# Sheet1.net
KiCad netlist of a schematic drawn in Altium Designer
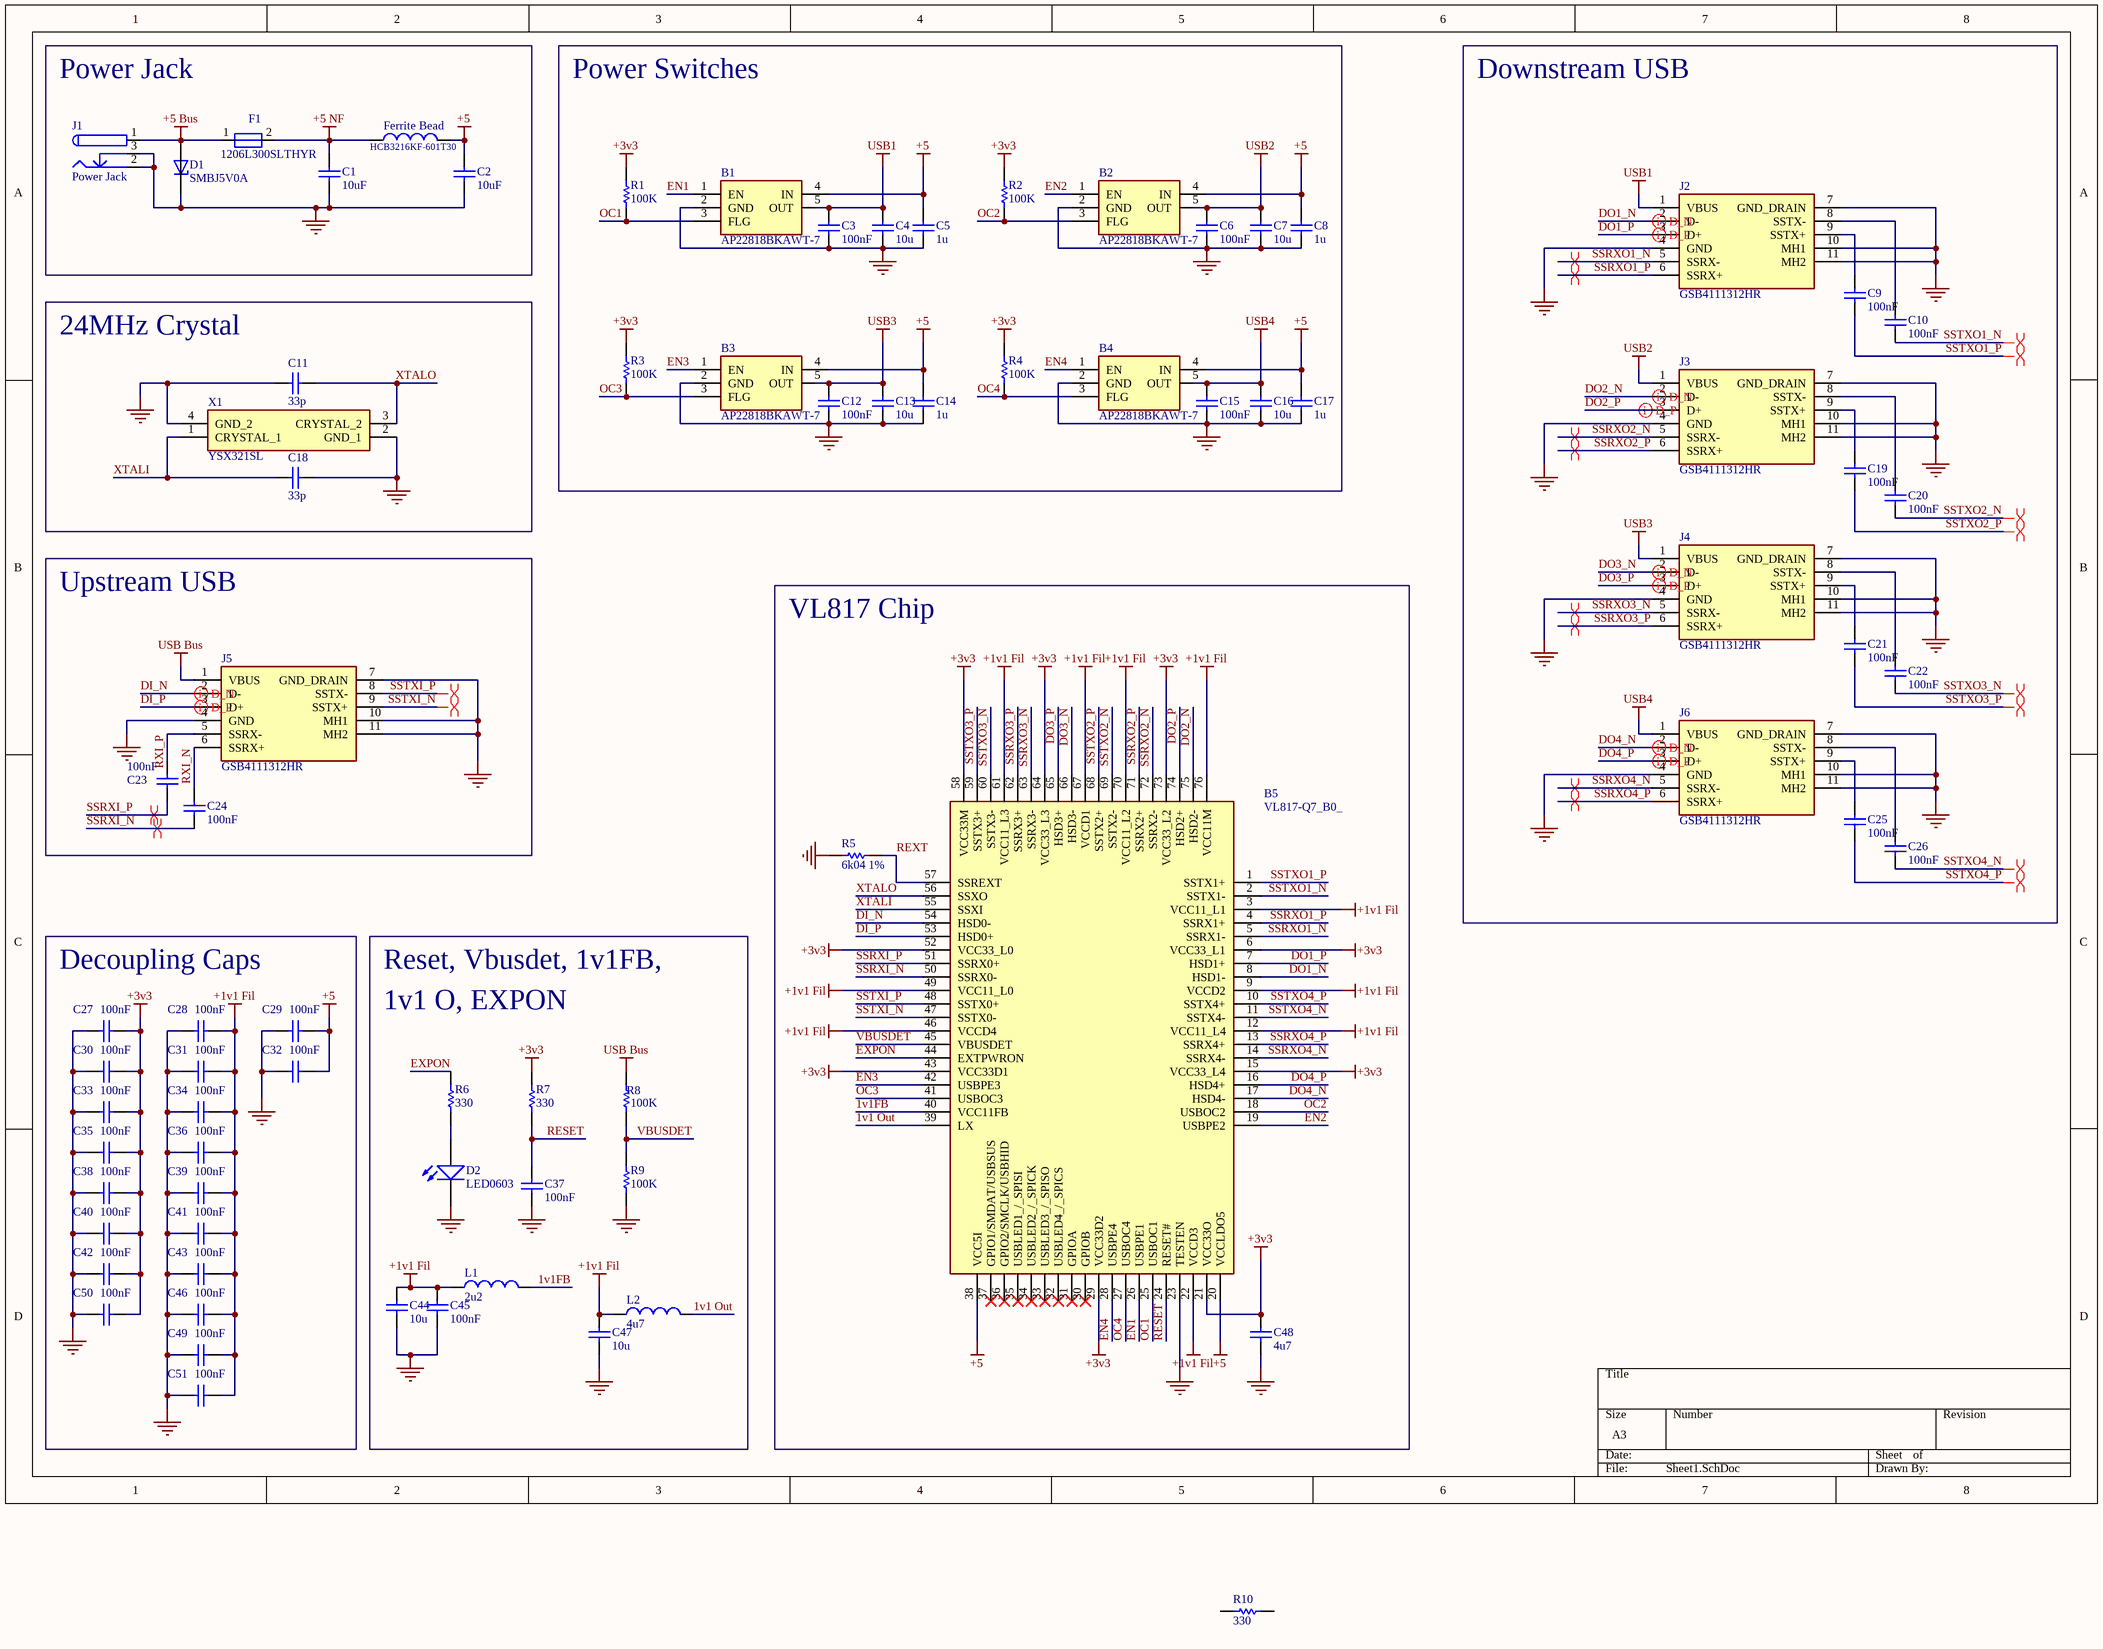
[diagram p0: Sheet1.SchDoc]

(export (version "E")
  (design (tool "Eeschema 10.0.6"))
  (components
    (comp (ref "B1")
      (value "AP22818BKAWT-7")
      (footprint "SOT95P280X100-5N")
      (description "USB Switch ICs USB Power Switch TSOT25 T&R 3K")
      (fields (field (name "MOUSER PART NUMBER") "621-AP22818BKAWT-7"))
      (libsource (lib "AP22818BKAWT-7") (part "AP22818BKAWT-7"))
    )
    (comp (ref "B2")
      (value "AP22818BKAWT-7")
      (footprint "SOT95P280X100-5N")
      (description "USB Switch ICs USB Power Switch TSOT25 T&R 3K")
      (fields (field (name "MOUSER PART NUMBER") "621-AP22818BKAWT-7"))
      (libsource (lib "AP22818BKAWT-7") (part "AP22818BKAWT-7"))
    )
    (comp (ref "B3")
      (value "AP22818BKAWT-7")
      (footprint "SOT95P280X100-5N")
      (description "USB Switch ICs USB Power Switch TSOT25 T&R 3K")
      (fields (field (name "MOUSER PART NUMBER") "621-AP22818BKAWT-7"))
      (libsource (lib "AP22818BKAWT-7") (part "AP22818BKAWT-7"))
    )
    (comp (ref "B4")
      (value "AP22818BKAWT-7")
      (footprint "SOT95P280X100-5N")
      (description "USB Switch ICs USB Power Switch TSOT25 T&R 3K")
      (fields (field (name "MOUSER PART NUMBER") "621-AP22818BKAWT-7"))
      (libsource (lib "AP22818BKAWT-7") (part "AP22818BKAWT-7"))
    )
    (comp (ref "B5")
      (value "VL817-Q7_B0_")
      (footprint "QFN40P900X900X90-77N-D")
      (description "QFN-76_9x9x04P USB ICs RoHS")
      (fields (field (name "MANUFACTURER_PART_NUMBER") "VL817-Q7(B0)"))
      (libsource (lib "VL817-Q7_B0_") (part "VL817-Q7_B0_"))
    )
    (comp (ref "C1")
      (value "10uF")
      (footprint "CAP1206")
      (description "CAP1206")
      (libsource (lib "CAP1206") (part "CAP1206"))
    )
    (comp (ref "C2")
      (value "10uF")
      (footprint "CAP1206")
      (description "CAP1206")
      (libsource (lib "CAP1206") (part "CAP1206"))
    )
    (comp (ref "C3")
      (value "100nF")
      (footprint "CAP0402")
      (description "CAP0402")
      (libsource (lib "CAP0402") (part "CAP0402"))
    )
    (comp (ref "C4")
      (value "10u")
      (footprint "CAP0603")
      (description "CAP0603")
      (libsource (lib "CAP0603") (part "CAP0603"))
    )
    (comp (ref "C5")
      (value "1u")
      (footprint "CAP0603")
      (description "CAP0603")
      (libsource (lib "CAP0603") (part "CAP0603"))
    )
    (comp (ref "C6")
      (value "100nF")
      (footprint "CAP0402")
      (description "CAP0402")
      (libsource (lib "CAP0402") (part "CAP0402"))
    )
    (comp (ref "C7")
      (value "10u")
      (footprint "CAP0603")
      (description "CAP0603")
      (libsource (lib "CAP0603") (part "CAP0603"))
    )
    (comp (ref "C8")
      (value "1u")
      (footprint "CAP0603")
      (description "CAP0603")
      (libsource (lib "CAP0603") (part "CAP0603"))
    )
    (comp (ref "C9")
      (value "100nF")
      (footprint "CAP0402")
      (description "CAP0402")
      (libsource (lib "CAP0402") (part "CAP0402"))
    )
    (comp (ref "C10")
      (value "100nF")
      (footprint "CAP0402")
      (description "CAP0402")
      (libsource (lib "CAP0402") (part "CAP0402"))
    )
    (comp (ref "C11")
      (value "33p")
      (footprint "CAP0402")
      (description "CAP0402")
      (libsource (lib "CAP0402") (part "CAP0402"))
    )
    (comp (ref "C12")
      (value "100nF")
      (footprint "CAP0402")
      (description "CAP0402")
      (libsource (lib "CAP0402") (part "CAP0402"))
    )
    (comp (ref "C13")
      (value "10u")
      (footprint "CAP0603")
      (description "CAP0603")
      (libsource (lib "CAP0603") (part "CAP0603"))
    )
    (comp (ref "C14")
      (value "1u")
      (footprint "CAP0603")
      (description "CAP0603")
      (libsource (lib "CAP0603") (part "CAP0603"))
    )
    (comp (ref "C15")
      (value "100nF")
      (footprint "CAP0402")
      (description "CAP0402")
      (libsource (lib "CAP0402") (part "CAP0402"))
    )
    (comp (ref "C16")
      (value "10u")
      (footprint "CAP0603")
      (description "CAP0603")
      (libsource (lib "CAP0603") (part "CAP0603"))
    )
    (comp (ref "C17")
      (value "1u")
      (footprint "CAP0603")
      (description "CAP0603")
      (libsource (lib "CAP0603") (part "CAP0603"))
    )
    (comp (ref "C18")
      (value "33p")
      (footprint "CAP0402")
      (description "CAP0402")
      (libsource (lib "CAP0402") (part "CAP0402"))
    )
    (comp (ref "C19")
      (value "100nF")
      (footprint "CAP0402")
      (description "CAP0402")
      (libsource (lib "CAP0402") (part "CAP0402"))
    )
    (comp (ref "C20")
      (value "100nF")
      (footprint "CAP0402")
      (description "CAP0402")
      (libsource (lib "CAP0402") (part "CAP0402"))
    )
    (comp (ref "C21")
      (value "100nF")
      (footprint "CAP0402")
      (description "CAP0402")
      (libsource (lib "CAP0402") (part "CAP0402"))
    )
    (comp (ref "C22")
      (value "100nF")
      (footprint "CAP0402")
      (description "CAP0402")
      (libsource (lib "CAP0402") (part "CAP0402"))
    )
    (comp (ref "C23")
      (value "100nF")
      (footprint "CAP0402")
      (description "CAP0402")
      (libsource (lib "CAP0402") (part "CAP0402"))
    )
    (comp (ref "C24")
      (value "100nF")
      (footprint "CAP0402")
      (description "CAP0402")
      (libsource (lib "CAP0402") (part "CAP0402"))
    )
    (comp (ref "C25")
      (value "100nF")
      (footprint "CAP0402")
      (description "CAP0402")
      (libsource (lib "CAP0402") (part "CAP0402"))
    )
    (comp (ref "C26")
      (value "100nF")
      (footprint "CAP0402")
      (description "CAP0402")
      (libsource (lib "CAP0402") (part "CAP0402"))
    )
    (comp (ref "C27")
      (value "100nF")
      (footprint "CAP0402")
      (description "CAP0402")
      (libsource (lib "CAP0402") (part "CAP0402"))
    )
    (comp (ref "C28")
      (value "100nF")
      (footprint "CAP0402")
      (description "CAP0402")
      (libsource (lib "CAP0402") (part "CAP0402"))
    )
    (comp (ref "C29")
      (value "100nF")
      (footprint "CAP0402")
      (description "CAP0402")
      (libsource (lib "CAP0402") (part "CAP0402"))
    )
    (comp (ref "C30")
      (value "100nF")
      (footprint "CAP0402")
      (description "CAP0402")
      (libsource (lib "CAP0402") (part "CAP0402"))
    )
    (comp (ref "C31")
      (value "100nF")
      (footprint "CAP0402")
      (description "CAP0402")
      (libsource (lib "CAP0402") (part "CAP0402"))
    )
    (comp (ref "C32")
      (value "100nF")
      (footprint "CAP0402")
      (description "CAP0402")
      (libsource (lib "CAP0402") (part "CAP0402"))
    )
    (comp (ref "C33")
      (value "100nF")
      (footprint "CAP0402")
      (description "CAP0402")
      (libsource (lib "CAP0402") (part "CAP0402"))
    )
    (comp (ref "C34")
      (value "100nF")
      (footprint "CAP0402")
      (description "CAP0402")
      (libsource (lib "CAP0402") (part "CAP0402"))
    )
    (comp (ref "C35")
      (value "100nF")
      (footprint "CAP0402")
      (description "CAP0402")
      (libsource (lib "CAP0402") (part "CAP0402"))
    )
    (comp (ref "C36")
      (value "100nF")
      (footprint "CAP0402")
      (description "CAP0402")
      (libsource (lib "CAP0402") (part "CAP0402"))
    )
    (comp (ref "C37")
      (value "100nF")
      (footprint "CAP0402")
      (description "CAP0402")
      (libsource (lib "CAP0402") (part "CAP0402"))
    )
    (comp (ref "C38")
      (value "100nF")
      (footprint "CAP0402")
      (description "CAP0402")
      (libsource (lib "CAP0402") (part "CAP0402"))
    )
    (comp (ref "C39")
      (value "100nF")
      (footprint "CAP0402")
      (description "CAP0402")
      (libsource (lib "CAP0402") (part "CAP0402"))
    )
    (comp (ref "C40")
      (value "100nF")
      (footprint "CAP0402")
      (description "CAP0402")
      (libsource (lib "CAP0402") (part "CAP0402"))
    )
    (comp (ref "C41")
      (value "100nF")
      (footprint "CAP0402")
      (description "CAP0402")
      (libsource (lib "CAP0402") (part "CAP0402"))
    )
    (comp (ref "C42")
      (value "100nF")
      (footprint "CAP0402")
      (description "CAP0402")
      (libsource (lib "CAP0402") (part "CAP0402"))
    )
    (comp (ref "C43")
      (value "100nF")
      (footprint "CAP0402")
      (description "CAP0402")
      (libsource (lib "CAP0402") (part "CAP0402"))
    )
    (comp (ref "C44")
      (value "10u")
      (footprint "CAP0603")
      (description "CAP0603")
      (libsource (lib "CAP0603") (part "CAP0603"))
    )
    (comp (ref "C45")
      (value "100nF")
      (footprint "CAP0402")
      (description "CAP0402")
      (libsource (lib "CAP0402") (part "CAP0402"))
    )
    (comp (ref "C46")
      (value "100nF")
      (footprint "CAP0402")
      (description "CAP0402")
      (libsource (lib "CAP0402") (part "CAP0402"))
    )
    (comp (ref "C47")
      (value "10u")
      (footprint "CAP0603")
      (description "CAP0603")
      (libsource (lib "CAP0603") (part "CAP0603"))
    )
    (comp (ref "C48")
      (value "4u7")
      (footprint "CAP0603")
      (description "CAP0603")
      (libsource (lib "CAP0603") (part "CAP0603"))
    )
    (comp (ref "C49")
      (value "100nF")
      (footprint "CAP0402")
      (description "CAP0402")
      (libsource (lib "CAP0402") (part "CAP0402"))
    )
    (comp (ref "C50")
      (value "100nF")
      (footprint "CAP0402")
      (description "CAP0402")
      (libsource (lib "CAP0402") (part "CAP0402"))
    )
    (comp (ref "C51")
      (value "100nF")
      (footprint "CAP0402")
      (description "CAP0402")
      (libsource (lib "CAP0402") (part "CAP0402"))
    )
    (comp (ref "D1")
      (value "SMBJ5V0A")
      (footprint "DIOM4336X265N")
      (fields (field (name "MF") "Fairchild Semiconductor"))
      (libsource (lib "SMBJ5V0A") (part "SMBJ5V0A"))
    )
    (comp (ref "D2")
      (value "LED0603")
      (footprint "LED_SMD_0603")
      (libsource (lib "LED_SMD_0603") (part "LED_SMD_0603"))
    )
    (comp (ref "F1")
      (value "1206L300SLTHYR")
      (footprint "FUSC3115X66N")
      (description "475 Series 1206 Fast-Acting Fuse")
      (fields (field (name "MF") "Littelfuse") (field (name "MP") "046602.5NRHF"))
      (libsource (lib "046602.5NRHF") (part "046602.5NRHF"))
    )
    (comp (ref "Ferrite Bead")
      (value "HCB3216KF-601T30")
      (footprint "IND1206")
      (description "IND1206")
      (libsource (lib "IND1206") (part "IND1206"))
    )
    (comp (ref "J1")
      (value "Power Jack")
      (footprint "Power Jack")
      (fields (field (name "DESIGNER") "Saeid Jorablo"))
      (libsource (lib "Library 1") (part "Power Jack"))
    )
    (comp (ref "J2")
      (value "GSB4111312HR")
      (footprint "GSB4111312HR")
      (libsource (lib "GSB4111312HR") (part "GSB4111312HR"))
    )
    (comp (ref "J3")
      (value "GSB4111312HR")
      (footprint "GSB4111312HR")
      (libsource (lib "GSB4111312HR") (part "GSB4111312HR"))
    )
    (comp (ref "J4")
      (value "GSB4111312HR")
      (footprint "GSB4111312HR")
      (libsource (lib "GSB4111312HR") (part "GSB4111312HR"))
    )
    (comp (ref "J5")
      (value "GSB4111312HR")
      (footprint "GSB4111312HR")
      (libsource (lib "GSB4111312HR") (part "GSB4111312HR"))
    )
    (comp (ref "J6")
      (value "GSB4111312HR")
      (footprint "GSB4111312HR")
      (libsource (lib "GSB4111312HR") (part "GSB4111312HR"))
    )
    (comp (ref "L1")
      (value "2u2")
      (footprint "IND0603")
      (description "IND0603")
      (libsource (lib "IND0603") (part "IND0603"))
    )
    (comp (ref "L2")
      (value "4u7")
      (footprint "IND0603")
      (description "IND0603")
      (libsource (lib "IND0603") (part "IND0603"))
    )
    (comp (ref "R1")
      (value "100K")
      (footprint "RES0603")
      (description "RES0603")
      (libsource (lib "RES0603") (part "RES0603"))
    )
    (comp (ref "R2")
      (value "100K")
      (footprint "RES0603")
      (description "RES0603")
      (libsource (lib "RES0603") (part "RES0603"))
    )
    (comp (ref "R3")
      (value "100K")
      (footprint "RES0603")
      (description "RES0603")
      (libsource (lib "RES0603") (part "RES0603"))
    )
    (comp (ref "R4")
      (value "100K")
      (footprint "RES0603")
      (description "RES0603")
      (libsource (lib "RES0603") (part "RES0603"))
    )
    (comp (ref "R5")
      (value "6k04 1%")
      (footprint "RES0603")
      (description "RES0603")
      (libsource (lib "RES0603") (part "RES0603"))
    )
    (comp (ref "R6")
      (value "330")
      (footprint "RES0603")
      (description "RES0603")
      (libsource (lib "RES0603") (part "RES0603"))
    )
    (comp (ref "R7")
      (value "330")
      (footprint "RES0603")
      (description "RES0603")
      (libsource (lib "RES0603") (part "RES0603"))
    )
    (comp (ref "R8")
      (value "100K")
      (footprint "RES0603")
      (description "RES0603")
      (libsource (lib "RES0603") (part "RES0603"))
    )
    (comp (ref "R9")
      (value "100K")
      (footprint "RES0603")
      (description "RES0603")
      (libsource (lib "RES0603") (part "RES0603"))
    )
    (comp (ref "R10")
      (value "330")
      (footprint "Res50")
      (description "Resistor 0.5")
      (fields
        (field (name "Comment") "Resistor vertical")
        (field (name "PUBLISHER") "Seyed mohsen ghasemian")
      )
      (libsource (lib "usefully_Library") (part "Resistor vertical"))
    )
    (comp (ref "X1")
      (value "YSX321SL")
      (footprint "YSX321SL")
      (description "Crystal")
      (libsource (lib "YSX321SL") (part "YSX321SL"))
    )
  )
  (nets
    (net (code "1") (name "+1v1 Fil") (class "Default")
      (node (ref "B5") (pin "12") (pinfunction "VCC11_L4_12") (pintype "passive"))
      (node (ref "B5") (pin "22") (pinfunction "VCCD3_22") (pintype "passive"))
      (node (ref "B5") (pin "3") (pinfunction "VCC11_L1_3") (pintype "passive"))
      (node (ref "B5") (pin "46") (pinfunction "VCCD4_46") (pintype "passive"))
      (node (ref "B5") (pin "49") (pinfunction "VCC11_L0_49") (pintype "passive"))
      (node (ref "B5") (pin "61") (pinfunction "VCC11_L3_61") (pintype "passive"))
      (node (ref "B5") (pin "67") (pinfunction "VCCD1_67") (pintype "passive"))
      (node (ref "B5") (pin "70") (pinfunction "VCC11_L2_70") (pintype "passive"))
      (node (ref "B5") (pin "76") (pinfunction "VCC11M_76") (pintype "passive"))
      (node (ref "B5") (pin "9") (pinfunction "VCCD2_9") (pintype "passive"))
      (node (ref "C28") (pin "2") (pinfunction "2_2") (pintype "passive"))
      (node (ref "C31") (pin "2") (pinfunction "2_2") (pintype "passive"))
      (node (ref "C34") (pin "2") (pinfunction "2_2") (pintype "passive"))
      (node (ref "C36") (pin "2") (pinfunction "2_2") (pintype "passive"))
      (node (ref "C39") (pin "2") (pinfunction "2_2") (pintype "passive"))
      (node (ref "C41") (pin "2") (pinfunction "2_2") (pintype "passive"))
      (node (ref "C43") (pin "2") (pinfunction "2_2") (pintype "passive"))
      (node (ref "C44") (pin "2") (pinfunction "2_2") (pintype "passive"))
      (node (ref "C45") (pin "2") (pinfunction "2_2") (pintype "passive"))
      (node (ref "C46") (pin "2") (pinfunction "2_2") (pintype "passive"))
      (node (ref "C47") (pin "2") (pinfunction "2_2") (pintype "passive"))
      (node (ref "C49") (pin "2") (pinfunction "2_2") (pintype "passive"))
      (node (ref "C51") (pin "2") (pinfunction "2_2") (pintype "passive"))
      (node (ref "L1") (pin "1") (pinfunction "1_1") (pintype "passive"))
      (node (ref "L2") (pin "1") (pinfunction "1_1") (pintype "passive"))
    )
    (net (code "2") (name "+3v3") (class "Default")
      (node (ref "B5") (pin "15") (pinfunction "VCC33_L4_15") (pintype "passive"))
      (node (ref "B5") (pin "21") (pinfunction "VCC33O_21") (pintype "passive"))
      (node (ref "B5") (pin "29") (pinfunction "VCC33D2_29") (pintype "passive"))
      (node (ref "B5") (pin "43") (pinfunction "VCC33D1_43") (pintype "passive"))
      (node (ref "B5") (pin "52") (pinfunction "VCC33_L0_52") (pintype "passive"))
      (node (ref "B5") (pin "58") (pinfunction "VCC33M_58") (pintype "passive"))
      (node (ref "B5") (pin "6") (pinfunction "VCC33_L1_6") (pintype "passive"))
      (node (ref "B5") (pin "64") (pinfunction "VCC33_L3_64") (pintype "passive"))
      (node (ref "B5") (pin "73") (pinfunction "VCC33_L2_73") (pintype "passive"))
      (node (ref "C27") (pin "2") (pinfunction "2_2") (pintype "passive"))
      (node (ref "C30") (pin "2") (pinfunction "2_2") (pintype "passive"))
      (node (ref "C33") (pin "2") (pinfunction "2_2") (pintype "passive"))
      (node (ref "C35") (pin "2") (pinfunction "2_2") (pintype "passive"))
      (node (ref "C38") (pin "2") (pinfunction "2_2") (pintype "passive"))
      (node (ref "C40") (pin "2") (pinfunction "2_2") (pintype "passive"))
      (node (ref "C42") (pin "2") (pinfunction "2_2") (pintype "passive"))
      (node (ref "C48") (pin "2") (pinfunction "2_2") (pintype "passive"))
      (node (ref "C50") (pin "2") (pinfunction "2_2") (pintype "passive"))
      (node (ref "R1") (pin "2") (pinfunction "2_2") (pintype "passive"))
      (node (ref "R2") (pin "2") (pinfunction "2_2") (pintype "passive"))
      (node (ref "R3") (pin "2") (pinfunction "2_2") (pintype "passive"))
      (node (ref "R4") (pin "2") (pinfunction "2_2") (pintype "passive"))
      (node (ref "R7") (pin "2") (pinfunction "2_2") (pintype "passive"))
    )
    (net (code "3") (name "+5") (class "Default")
      (node (ref "B1") (pin "4") (pinfunction "IN_4") (pintype "passive"))
      (node (ref "B2") (pin "4") (pinfunction "IN_4") (pintype "passive"))
      (node (ref "B3") (pin "4") (pinfunction "IN_4") (pintype "passive"))
      (node (ref "B4") (pin "4") (pinfunction "IN_4") (pintype "passive"))
      (node (ref "B5") (pin "20") (pinfunction "VCCLDO5_20") (pintype "passive"))
      (node (ref "B5") (pin "38") (pinfunction "VCC5I_38") (pintype "passive"))
      (node (ref "C14") (pin "2") (pinfunction "2_2") (pintype "passive"))
      (node (ref "C17") (pin "2") (pinfunction "2_2") (pintype "passive"))
      (node (ref "C2") (pin "2") (pinfunction "2_2") (pintype "passive"))
      (node (ref "C29") (pin "2") (pinfunction "2_2") (pintype "passive"))
      (node (ref "C32") (pin "2") (pinfunction "2_2") (pintype "passive"))
      (node (ref "C5") (pin "2") (pinfunction "2_2") (pintype "passive"))
      (node (ref "C8") (pin "2") (pinfunction "2_2") (pintype "passive"))
      (node (ref "Ferrite Bead") (pin "2") (pinfunction "2_2") (pintype "passive"))
    )
    (net (code "4") (name "+5 Bus") (class "Default")
      (node (ref "D1") (pin "A") (pinfunction "A_A") (pintype "passive"))
      (node (ref "F1") (pin "1") (pinfunction "1_1") (pintype "passive"))
      (node (ref "J1") (pin "1") (pinfunction "1_1") (pintype "power_in"))
    )
    (net (code "5") (name "+5 NF") (class "Default")
      (node (ref "C1") (pin "2") (pinfunction "2_2") (pintype "passive"))
      (node (ref "F1") (pin "2") (pinfunction "2_2") (pintype "passive"))
      (node (ref "Ferrite Bead") (pin "1") (pinfunction "1_1") (pintype "passive"))
    )
    (net (code "6") (name "/1v1 Out") (class "Default")
      (node (ref "B5") (pin "39") (pinfunction "LX_39") (pintype "passive"))
      (node (ref "L2") (pin "2") (pinfunction "2_2") (pintype "passive"))
    )
    (net (code "7") (name "/1v1FB") (class "Default")
      (node (ref "B5") (pin "40") (pinfunction "VCC11FB_40") (pintype "passive"))
      (node (ref "L1") (pin "2") (pinfunction "2_2") (pintype "passive"))
    )
    (net (code "8") (name "/DI_N") (class "Default")
      (node (ref "B5") (pin "54") (pinfunction "HSD0-_54") (pintype "passive"))
      (node (ref "J5") (pin "2") (pinfunction "D-_2") (pintype "passive"))
    )
    (net (code "9") (name "/DI_P") (class "Default")
      (node (ref "B5") (pin "53") (pinfunction "HSD0+_53") (pintype "passive"))
      (node (ref "J5") (pin "3") (pinfunction "D+_3") (pintype "passive"))
    )
    (net (code "10") (name "/DO1_N") (class "Default")
      (node (ref "B5") (pin "8") (pinfunction "HSD1-_8") (pintype "passive"))
      (node (ref "J2") (pin "2") (pinfunction "D-_2") (pintype "passive"))
    )
    (net (code "11") (name "/DO1_P") (class "Default")
      (node (ref "B5") (pin "7") (pinfunction "HSD1+_7") (pintype "passive"))
      (node (ref "J2") (pin "3") (pinfunction "D+_3") (pintype "passive"))
    )
    (net (code "12") (name "/DO2_N") (class "Default")
      (node (ref "B5") (pin "75") (pinfunction "HSD2-_75") (pintype "passive"))
      (node (ref "J3") (pin "2") (pinfunction "D-_2") (pintype "passive"))
    )
    (net (code "13") (name "/DO2_P") (class "Default")
      (node (ref "B5") (pin "74") (pinfunction "HSD2+_74") (pintype "passive"))
      (node (ref "J3") (pin "3") (pinfunction "D+_3") (pintype "passive"))
    )
    (net (code "14") (name "/DO3_N") (class "Default")
      (node (ref "B5") (pin "66") (pinfunction "HSD3-_66") (pintype "passive"))
      (node (ref "J4") (pin "2") (pinfunction "D-_2") (pintype "passive"))
    )
    (net (code "15") (name "/DO3_P") (class "Default")
      (node (ref "B5") (pin "65") (pinfunction "HSD3+_65") (pintype "passive"))
      (node (ref "J4") (pin "3") (pinfunction "D+_3") (pintype "passive"))
    )
    (net (code "16") (name "/DO4_N") (class "Default")
      (node (ref "B5") (pin "17") (pinfunction "HSD4-_17") (pintype "passive"))
      (node (ref "J6") (pin "2") (pinfunction "D-_2") (pintype "passive"))
    )
    (net (code "17") (name "/DO4_P") (class "Default")
      (node (ref "B5") (pin "16") (pinfunction "HSD4+_16") (pintype "passive"))
      (node (ref "J6") (pin "3") (pinfunction "D+_3") (pintype "passive"))
    )
    (net (code "18") (name "/EN1") (class "Default")
      (node (ref "B1") (pin "1") (pinfunction "EN_1") (pintype "passive"))
      (node (ref "B5") (pin "26") (pinfunction "USBPE1_26") (pintype "passive"))
    )
    (net (code "19") (name "/EN2") (class "Default")
      (node (ref "B2") (pin "1") (pinfunction "EN_1") (pintype "passive"))
      (node (ref "B5") (pin "19") (pinfunction "USBPE2_19") (pintype "passive"))
    )
    (net (code "20") (name "/EN3") (class "Default")
      (node (ref "B3") (pin "1") (pinfunction "EN_1") (pintype "passive"))
      (node (ref "B5") (pin "42") (pinfunction "USBPE3_42") (pintype "passive"))
    )
    (net (code "21") (name "/EN4") (class "Default")
      (node (ref "B4") (pin "1") (pinfunction "EN_1") (pintype "passive"))
      (node (ref "B5") (pin "28") (pinfunction "USBPE4_28") (pintype "passive"))
    )
    (net (code "22") (name "/EXPON") (class "Default")
      (node (ref "B5") (pin "44") (pinfunction "EXTPWRON_44") (pintype "passive"))
      (node (ref "R6") (pin "2") (pinfunction "2_2") (pintype "passive"))
    )
    (net (code "23") (name "/OC1") (class "Default")
      (node (ref "B1") (pin "3") (pinfunction "FLG_3") (pintype "passive"))
      (node (ref "B5") (pin "25") (pinfunction "USBOC1_25") (pintype "passive"))
      (node (ref "R1") (pin "1") (pinfunction "1_1") (pintype "passive"))
    )
    (net (code "24") (name "/OC2") (class "Default")
      (node (ref "B2") (pin "3") (pinfunction "FLG_3") (pintype "passive"))
      (node (ref "B5") (pin "18") (pinfunction "USBOC2_18") (pintype "passive"))
      (node (ref "R2") (pin "1") (pinfunction "1_1") (pintype "passive"))
    )
    (net (code "25") (name "/OC3") (class "Default")
      (node (ref "B3") (pin "3") (pinfunction "FLG_3") (pintype "passive"))
      (node (ref "B5") (pin "41") (pinfunction "USBOC3_41") (pintype "passive"))
      (node (ref "R3") (pin "1") (pinfunction "1_1") (pintype "passive"))
    )
    (net (code "26") (name "/OC4") (class "Default")
      (node (ref "B4") (pin "3") (pinfunction "FLG_3") (pintype "passive"))
      (node (ref "B5") (pin "27") (pinfunction "USBOC4_27") (pintype "passive"))
      (node (ref "R4") (pin "1") (pinfunction "1_1") (pintype "passive"))
    )
    (net (code "27") (name "/RESET") (class "Default")
      (node (ref "B5") (pin "24") (pinfunction "RESET#_24") (pintype "passive"))
      (node (ref "C37") (pin "2") (pinfunction "2_2") (pintype "passive"))
      (node (ref "R7") (pin "1") (pinfunction "1_1") (pintype "passive"))
    )
    (net (code "28") (name "/REXT") (class "Default")
      (node (ref "B5") (pin "57") (pinfunction "SSREXT_57") (pintype "passive"))
      (node (ref "R5") (pin "1") (pinfunction "1_1") (pintype "passive"))
    )
    (net (code "29") (name "/RXI_N") (class "Default")
      (node (ref "C24") (pin "2") (pinfunction "2_2") (pintype "passive"))
      (node (ref "J5") (pin "6") (pinfunction "SSRX+_6") (pintype "passive"))
    )
    (net (code "30") (name "/RXI_P") (class "Default")
      (node (ref "C23") (pin "2") (pinfunction "2_2") (pintype "passive"))
      (node (ref "J5") (pin "5") (pinfunction "SSRX-_5") (pintype "passive"))
    )
    (net (code "31") (name "/SSRXI_N") (class "Default")
      (node (ref "B5") (pin "50") (pinfunction "SSRX0-_50") (pintype "passive"))
      (node (ref "C24") (pin "1") (pinfunction "1_1") (pintype "passive"))
    )
    (net (code "32") (name "/SSRXI_P") (class "Default")
      (node (ref "B5") (pin "51") (pinfunction "SSRX0+_51") (pintype "passive"))
      (node (ref "C23") (pin "1") (pinfunction "1_1") (pintype "passive"))
    )
    (net (code "33") (name "/SSRXO1_N") (class "Default")
      (node (ref "B5") (pin "5") (pinfunction "SSRX1-_5") (pintype "passive"))
      (node (ref "J2") (pin "5") (pinfunction "SSRX-_5") (pintype "passive"))
    )
    (net (code "34") (name "/SSRXO1_P") (class "Default")
      (node (ref "B5") (pin "4") (pinfunction "SSRX1+_4") (pintype "passive"))
      (node (ref "J2") (pin "6") (pinfunction "SSRX+_6") (pintype "passive"))
    )
    (net (code "35") (name "/SSRXO2_N") (class "Default")
      (node (ref "B5") (pin "72") (pinfunction "SSRX2-_72") (pintype "passive"))
      (node (ref "J3") (pin "5") (pinfunction "SSRX-_5") (pintype "passive"))
    )
    (net (code "36") (name "/SSRXO2_P") (class "Default")
      (node (ref "B5") (pin "71") (pinfunction "SSRX2+_71") (pintype "passive"))
      (node (ref "J3") (pin "6") (pinfunction "SSRX+_6") (pintype "passive"))
    )
    (net (code "37") (name "/SSRXO3_N") (class "Default")
      (node (ref "B5") (pin "63") (pinfunction "SSRX3-_63") (pintype "passive"))
      (node (ref "J4") (pin "5") (pinfunction "SSRX-_5") (pintype "passive"))
    )
    (net (code "38") (name "/SSRXO3_P") (class "Default")
      (node (ref "B5") (pin "62") (pinfunction "SSRX3+_62") (pintype "passive"))
      (node (ref "J4") (pin "6") (pinfunction "SSRX+_6") (pintype "passive"))
    )
    (net (code "39") (name "/SSRXO4_N") (class "Default")
      (node (ref "B5") (pin "14") (pinfunction "SSRX4-_14") (pintype "passive"))
      (node (ref "J6") (pin "5") (pinfunction "SSRX-_5") (pintype "passive"))
    )
    (net (code "40") (name "/SSRXO4_P") (class "Default")
      (node (ref "B5") (pin "13") (pinfunction "SSRX4+_13") (pintype "passive"))
      (node (ref "J6") (pin "6") (pinfunction "SSRX+_6") (pintype "passive"))
    )
    (net (code "41") (name "/SSTXI_N") (class "Default")
      (node (ref "B5") (pin "47") (pinfunction "SSTX0-_47") (pintype "passive"))
      (node (ref "J5") (pin "9") (pinfunction "SSTX+_9") (pintype "passive"))
    )
    (net (code "42") (name "/SSTXI_P") (class "Default")
      (node (ref "B5") (pin "48") (pinfunction "SSTX0+_48") (pintype "passive"))
      (node (ref "J5") (pin "8") (pinfunction "SSTX-_8") (pintype "passive"))
    )
    (net (code "43") (name "/SSTXO1_N") (class "Default")
      (node (ref "B5") (pin "2") (pinfunction "SSTX1-_2") (pintype "passive"))
      (node (ref "C10") (pin "1") (pinfunction "1_1") (pintype "passive"))
    )
    (net (code "44") (name "/SSTXO1_P") (class "Default")
      (node (ref "B5") (pin "1") (pinfunction "SSTX1+_1") (pintype "passive"))
      (node (ref "C9") (pin "1") (pinfunction "1_1") (pintype "passive"))
    )
    (net (code "45") (name "/SSTXO2_N") (class "Default")
      (node (ref "B5") (pin "69") (pinfunction "SSTX2-_69") (pintype "passive"))
      (node (ref "C20") (pin "1") (pinfunction "1_1") (pintype "passive"))
    )
    (net (code "46") (name "/SSTXO2_P") (class "Default")
      (node (ref "B5") (pin "68") (pinfunction "SSTX2+_68") (pintype "passive"))
      (node (ref "C19") (pin "1") (pinfunction "1_1") (pintype "passive"))
    )
    (net (code "47") (name "/SSTXO3_N") (class "Default")
      (node (ref "B5") (pin "60") (pinfunction "SSTX3-_60") (pintype "passive"))
      (node (ref "C22") (pin "1") (pinfunction "1_1") (pintype "passive"))
    )
    (net (code "48") (name "/SSTXO3_P") (class "Default")
      (node (ref "B5") (pin "59") (pinfunction "SSTX3+_59") (pintype "passive"))
      (node (ref "C21") (pin "1") (pinfunction "1_1") (pintype "passive"))
    )
    (net (code "49") (name "/SSTXO4_N") (class "Default")
      (node (ref "B5") (pin "11") (pinfunction "SSTX4-_11") (pintype "passive"))
      (node (ref "C26") (pin "1") (pinfunction "1_1") (pintype "passive"))
    )
    (net (code "50") (name "/SSTXO4_P") (class "Default")
      (node (ref "B5") (pin "10") (pinfunction "SSTX4+_10") (pintype "passive"))
      (node (ref "C25") (pin "1") (pinfunction "1_1") (pintype "passive"))
    )
    (net (code "51") (name "/VBUSDET") (class "Default")
      (node (ref "B5") (pin "45") (pinfunction "VBUSDET_45") (pintype "passive"))
      (node (ref "R8") (pin "1") (pinfunction "1_1") (pintype "passive"))
      (node (ref "R9") (pin "2") (pinfunction "2_2") (pintype "passive"))
    )
    (net (code "52") (name "/XTALI") (class "Default")
      (node (ref "B5") (pin "55") (pinfunction "SSXI_55") (pintype "passive"))
      (node (ref "C18") (pin "2") (pinfunction "2_2") (pintype "passive"))
      (node (ref "X1") (pin "1") (pinfunction "CRYSTAL_1_1") (pintype "passive"))
    )
    (net (code "53") (name "/XTALO") (class "Default")
      (node (ref "B5") (pin "56") (pinfunction "SSXO_56") (pintype "passive"))
      (node (ref "C11") (pin "1") (pinfunction "1_1") (pintype "passive"))
      (node (ref "X1") (pin "3") (pinfunction "CRYSTAL_2_3") (pintype "passive"))
    )
    (net (code "54") (name "GND") (class "Default")
      (node (ref "B1") (pin "2") (pinfunction "GND_2") (pintype "passive"))
      (node (ref "B2") (pin "2") (pinfunction "GND_2") (pintype "passive"))
      (node (ref "B3") (pin "2") (pinfunction "GND_2") (pintype "passive"))
      (node (ref "B4") (pin "2") (pinfunction "GND_2") (pintype "passive"))
      (node (ref "B5") (pin "23") (pinfunction "TESTEN_23") (pintype "passive"))
      (node (ref "C1") (pin "1") (pinfunction "1_1") (pintype "passive"))
      (node (ref "C11") (pin "2") (pinfunction "2_2") (pintype "passive"))
      (node (ref "C12") (pin "1") (pinfunction "1_1") (pintype "passive"))
      (node (ref "C13") (pin "1") (pinfunction "1_1") (pintype "passive"))
      (node (ref "C14") (pin "1") (pinfunction "1_1") (pintype "passive"))
      (node (ref "C15") (pin "1") (pinfunction "1_1") (pintype "passive"))
      (node (ref "C16") (pin "1") (pinfunction "1_1") (pintype "passive"))
      (node (ref "C17") (pin "1") (pinfunction "1_1") (pintype "passive"))
      (node (ref "C18") (pin "1") (pinfunction "1_1") (pintype "passive"))
      (node (ref "C2") (pin "1") (pinfunction "1_1") (pintype "passive"))
      (node (ref "C27") (pin "1") (pinfunction "1_1") (pintype "passive"))
      (node (ref "C28") (pin "1") (pinfunction "1_1") (pintype "passive"))
      (node (ref "C29") (pin "1") (pinfunction "1_1") (pintype "passive"))
      (node (ref "C3") (pin "1") (pinfunction "1_1") (pintype "passive"))
      (node (ref "C30") (pin "1") (pinfunction "1_1") (pintype "passive"))
      (node (ref "C31") (pin "1") (pinfunction "1_1") (pintype "passive"))
      (node (ref "C32") (pin "1") (pinfunction "1_1") (pintype "passive"))
      (node (ref "C33") (pin "1") (pinfunction "1_1") (pintype "passive"))
      (node (ref "C34") (pin "1") (pinfunction "1_1") (pintype "passive"))
      (node (ref "C35") (pin "1") (pinfunction "1_1") (pintype "passive"))
      (node (ref "C36") (pin "1") (pinfunction "1_1") (pintype "passive"))
      (node (ref "C37") (pin "1") (pinfunction "1_1") (pintype "passive"))
      (node (ref "C38") (pin "1") (pinfunction "1_1") (pintype "passive"))
      (node (ref "C39") (pin "1") (pinfunction "1_1") (pintype "passive"))
      (node (ref "C4") (pin "1") (pinfunction "1_1") (pintype "passive"))
      (node (ref "C40") (pin "1") (pinfunction "1_1") (pintype "passive"))
      (node (ref "C41") (pin "1") (pinfunction "1_1") (pintype "passive"))
      (node (ref "C42") (pin "1") (pinfunction "1_1") (pintype "passive"))
      (node (ref "C43") (pin "1") (pinfunction "1_1") (pintype "passive"))
      (node (ref "C44") (pin "1") (pinfunction "1_1") (pintype "passive"))
      (node (ref "C45") (pin "1") (pinfunction "1_1") (pintype "passive"))
      (node (ref "C46") (pin "1") (pinfunction "1_1") (pintype "passive"))
      (node (ref "C47") (pin "1") (pinfunction "1_1") (pintype "passive"))
      (node (ref "C48") (pin "1") (pinfunction "1_1") (pintype "passive"))
      (node (ref "C49") (pin "1") (pinfunction "1_1") (pintype "passive"))
      (node (ref "C5") (pin "1") (pinfunction "1_1") (pintype "passive"))
      (node (ref "C50") (pin "1") (pinfunction "1_1") (pintype "passive"))
      (node (ref "C51") (pin "1") (pinfunction "1_1") (pintype "passive"))
      (node (ref "C6") (pin "1") (pinfunction "1_1") (pintype "passive"))
      (node (ref "C7") (pin "1") (pinfunction "1_1") (pintype "passive"))
      (node (ref "C8") (pin "1") (pinfunction "1_1") (pintype "passive"))
      (node (ref "D1") (pin "C") (pinfunction "C_C") (pintype "passive"))
      (node (ref "D2") (pin "1") (pinfunction "K_1") (pintype "passive"))
      (node (ref "J1") (pin "2") (pinfunction "2_2") (pintype "power_in"))
      (node (ref "J1") (pin "3") (pinfunction "3_3") (pintype "power_in"))
      (node (ref "J2") (pin "10") (pinfunction "MH1_10") (pintype "passive"))
      (node (ref "J2") (pin "11") (pinfunction "MH2_11") (pintype "passive"))
      (node (ref "J2") (pin "4") (pinfunction "GND_4") (pintype "passive"))
      (node (ref "J2") (pin "7") (pinfunction "GND_DRAIN_7") (pintype "passive"))
      (node (ref "J3") (pin "10") (pinfunction "MH1_10") (pintype "passive"))
      (node (ref "J3") (pin "11") (pinfunction "MH2_11") (pintype "passive"))
      (node (ref "J3") (pin "4") (pinfunction "GND_4") (pintype "passive"))
      (node (ref "J3") (pin "7") (pinfunction "GND_DRAIN_7") (pintype "passive"))
      (node (ref "J4") (pin "10") (pinfunction "MH1_10") (pintype "passive"))
      (node (ref "J4") (pin "11") (pinfunction "MH2_11") (pintype "passive"))
      (node (ref "J4") (pin "4") (pinfunction "GND_4") (pintype "passive"))
      (node (ref "J4") (pin "7") (pinfunction "GND_DRAIN_7") (pintype "passive"))
      (node (ref "J5") (pin "10") (pinfunction "MH1_10") (pintype "passive"))
      (node (ref "J5") (pin "11") (pinfunction "MH2_11") (pintype "passive"))
      (node (ref "J5") (pin "4") (pinfunction "GND_4") (pintype "passive"))
      (node (ref "J5") (pin "7") (pinfunction "GND_DRAIN_7") (pintype "passive"))
      (node (ref "J6") (pin "10") (pinfunction "MH1_10") (pintype "passive"))
      (node (ref "J6") (pin "11") (pinfunction "MH2_11") (pintype "passive"))
      (node (ref "J6") (pin "4") (pinfunction "GND_4") (pintype "passive"))
      (node (ref "J6") (pin "7") (pinfunction "GND_DRAIN_7") (pintype "passive"))
      (node (ref "R5") (pin "2") (pinfunction "2_2") (pintype "passive"))
      (node (ref "R9") (pin "1") (pinfunction "1_1") (pintype "passive"))
      (node (ref "X1") (pin "2") (pinfunction "GND_1_2") (pintype "passive"))
      (node (ref "X1") (pin "4") (pinfunction "GND_2_4") (pintype "passive"))
    )
    (net (code "55") (name "Net-(D2-A)") (class "Default")
      (node (ref "D2") (pin "2") (pinfunction "A_2") (pintype "passive"))
      (node (ref "R6") (pin "1") (pinfunction "1_1") (pintype "passive"))
    )
    (net (code "56") (name "Net-(J2-SSTX+)") (class "Default")
      (node (ref "C9") (pin "2") (pinfunction "2_2") (pintype "passive"))
      (node (ref "J2") (pin "9") (pinfunction "SSTX+_9") (pintype "passive"))
    )
    (net (code "57") (name "Net-(J2-SSTX-)") (class "Default")
      (node (ref "C10") (pin "2") (pinfunction "2_2") (pintype "passive"))
      (node (ref "J2") (pin "8") (pinfunction "SSTX-_8") (pintype "passive"))
    )
    (net (code "58") (name "Net-(J3-SSTX+)") (class "Default")
      (node (ref "C19") (pin "2") (pinfunction "2_2") (pintype "passive"))
      (node (ref "J3") (pin "9") (pinfunction "SSTX+_9") (pintype "passive"))
    )
    (net (code "59") (name "Net-(J3-SSTX-)") (class "Default")
      (node (ref "C20") (pin "2") (pinfunction "2_2") (pintype "passive"))
      (node (ref "J3") (pin "8") (pinfunction "SSTX-_8") (pintype "passive"))
    )
    (net (code "60") (name "Net-(J4-SSTX+)") (class "Default")
      (node (ref "C21") (pin "2") (pinfunction "2_2") (pintype "passive"))
      (node (ref "J4") (pin "9") (pinfunction "SSTX+_9") (pintype "passive"))
    )
    (net (code "61") (name "Net-(J4-SSTX-)") (class "Default")
      (node (ref "C22") (pin "2") (pinfunction "2_2") (pintype "passive"))
      (node (ref "J4") (pin "8") (pinfunction "SSTX-_8") (pintype "passive"))
    )
    (net (code "62") (name "Net-(J6-SSTX+)") (class "Default")
      (node (ref "C25") (pin "2") (pinfunction "2_2") (pintype "passive"))
      (node (ref "J6") (pin "9") (pinfunction "SSTX+_9") (pintype "passive"))
    )
    (net (code "63") (name "Net-(J6-SSTX-)") (class "Default")
      (node (ref "C26") (pin "2") (pinfunction "2_2") (pintype "passive"))
      (node (ref "J6") (pin "8") (pinfunction "SSTX-_8") (pintype "passive"))
    )
    (net (code "64") (name "USB Bus") (class "Default")
      (node (ref "J5") (pin "1") (pinfunction "VBUS_1") (pintype "passive"))
      (node (ref "R8") (pin "2") (pinfunction "2_2") (pintype "passive"))
    )
    (net (code "65") (name "USB1") (class "Default")
      (node (ref "B1") (pin "5") (pinfunction "OUT_5") (pintype "passive"))
      (node (ref "C3") (pin "2") (pinfunction "2_2") (pintype "passive"))
      (node (ref "C4") (pin "2") (pinfunction "2_2") (pintype "passive"))
      (node (ref "J2") (pin "1") (pinfunction "VBUS_1") (pintype "passive"))
    )
    (net (code "66") (name "USB2") (class "Default")
      (node (ref "B2") (pin "5") (pinfunction "OUT_5") (pintype "passive"))
      (node (ref "C6") (pin "2") (pinfunction "2_2") (pintype "passive"))
      (node (ref "C7") (pin "2") (pinfunction "2_2") (pintype "passive"))
      (node (ref "J3") (pin "1") (pinfunction "VBUS_1") (pintype "passive"))
    )
    (net (code "67") (name "USB3") (class "Default")
      (node (ref "B3") (pin "5") (pinfunction "OUT_5") (pintype "passive"))
      (node (ref "C12") (pin "2") (pinfunction "2_2") (pintype "passive"))
      (node (ref "C13") (pin "2") (pinfunction "2_2") (pintype "passive"))
      (node (ref "J4") (pin "1") (pinfunction "VBUS_1") (pintype "passive"))
    )
    (net (code "68") (name "USB4") (class "Default")
      (node (ref "B4") (pin "5") (pinfunction "OUT_5") (pintype "passive"))
      (node (ref "C15") (pin "2") (pinfunction "2_2") (pintype "passive"))
      (node (ref "C16") (pin "2") (pinfunction "2_2") (pintype "passive"))
      (node (ref "J6") (pin "1") (pinfunction "VBUS_1") (pintype "passive"))
    )
    (net (code "69") (name "unconnected-(B5-GPIO1{slash}SMDAT{slash}USBSUS-Pad37)") (class "Default")
      (node (ref "B5") (pin "37") (pinfunction "GPIO1/SMDAT/USBSUS_37") (pintype "passive+no_connect"))
    )
    (net (code "70") (name "unconnected-(B5-GPIO2{slash}SMCLK{slash}USBHID-Pad36)") (class "Default")
      (node (ref "B5") (pin "36") (pinfunction "GPIO2/SMCLK/USBHID_36") (pintype "passive+no_connect"))
    )
    (net (code "71") (name "unconnected-(B5-GPIOA-Pad31)") (class "Default")
      (node (ref "B5") (pin "31") (pinfunction "GPIOA_31") (pintype "passive+no_connect"))
    )
    (net (code "72") (name "unconnected-(B5-GPIOB-Pad30)") (class "Default")
      (node (ref "B5") (pin "30") (pinfunction "GPIOB_30") (pintype "passive+no_connect"))
    )
    (net (code "73") (name "unconnected-(B5-USBLED1_{slash}_SPISI-Pad35)") (class "Default")
      (node (ref "B5") (pin "35") (pinfunction "USBLED1_/_SPISI_35") (pintype "passive+no_connect"))
    )
    (net (code "74") (name "unconnected-(B5-USBLED2_{slash}_SPICK-Pad34)") (class "Default")
      (node (ref "B5") (pin "34") (pinfunction "USBLED2_/_SPICK_34") (pintype "passive+no_connect"))
    )
    (net (code "75") (name "unconnected-(B5-USBLED3_{slash}_SPISO-Pad33)") (class "Default")
      (node (ref "B5") (pin "33") (pinfunction "USBLED3_/_SPISO_33") (pintype "passive+no_connect"))
    )
    (net (code "76") (name "unconnected-(B5-USBLED4_{slash}_SPICS-Pad32)") (class "Default")
      (node (ref "B5") (pin "32") (pinfunction "USBLED4_/_SPICS_32") (pintype "passive+no_connect"))
    )
    (net (code "77") (name "unconnected-(R10-Pad1)") (class "Default")
      (node (ref "R10") (pin "1") (pinfunction "1_1") (pintype "passive"))
    )
    (net (code "78") (name "unconnected-(R10-Pad2)") (class "Default")
      (node (ref "R10") (pin "2") (pinfunction "2_2") (pintype "passive"))
    )
  )
)
